# RPi_433MHz_Interface_Board.net
KiCad netlist of a schematic drawn in EAGLE
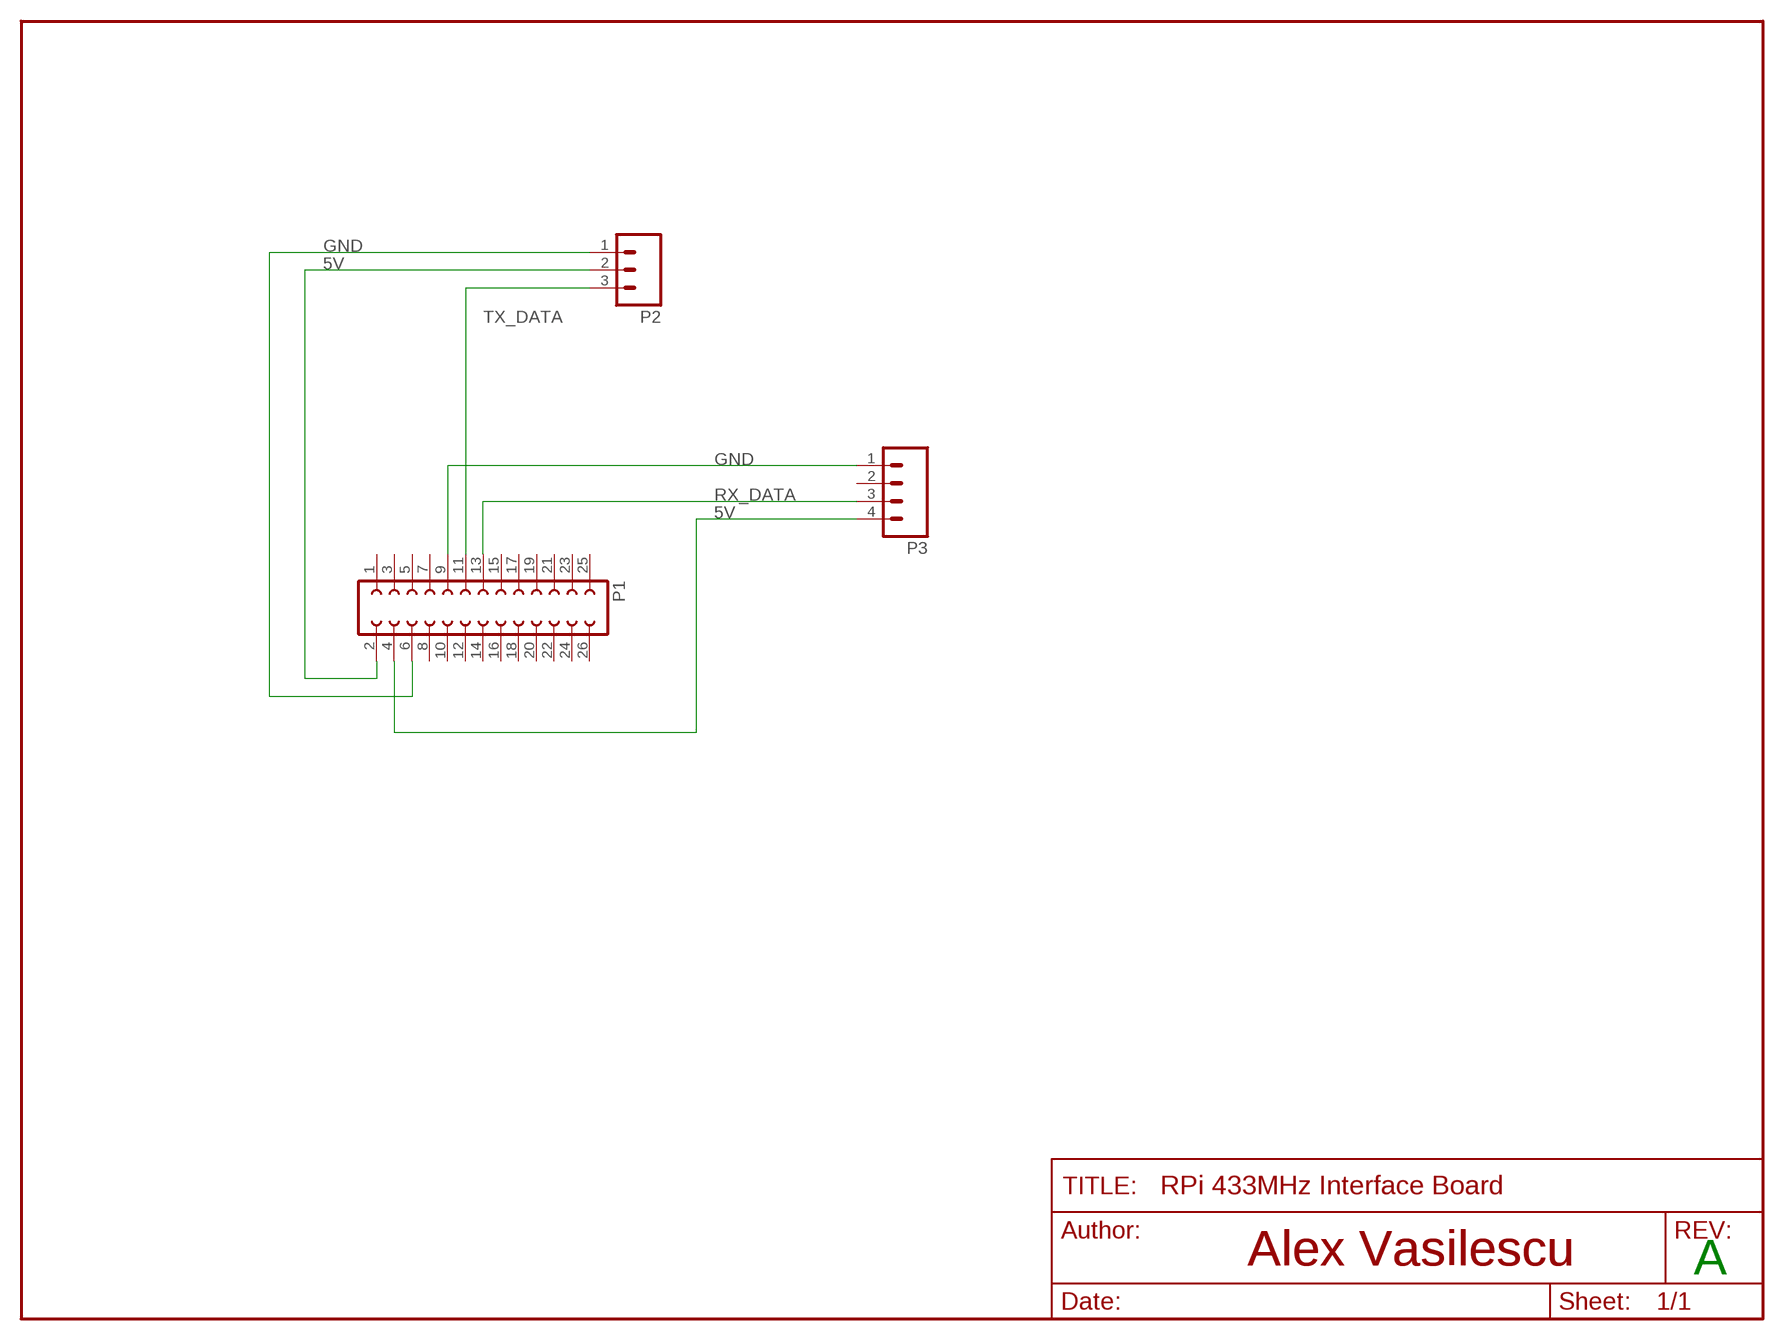
[diagram p0: schematic, sheet 1]

(export (version "E")
  (design (tool "Eeschema 10.0.6"))
  (components
    (comp (ref "P1")
      (value "FE13-2")
      (footprint "eagle-import:FE13-2")
      (libsource (lib "eagle-import") (part "FE13-2"))
    )
    (comp (ref "P2")
      (value "M03POLAR")
      (footprint "eagle-import:MOLEX-1X3")
      (libsource (lib "eagle-import") (part "M03POLAR"))
    )
    (comp (ref "P3")
      (value "M04POLAR")
      (footprint "eagle-import:MOLEX-1X4")
      (libsource (lib "eagle-import") (part "M04POLAR"))
    )
    (comp (ref "U$1")
      (value "AV-LOGO")
      (footprint "eagle-import:AV-LOGO")
      (libsource (lib "eagle-import") (part "AV-LOGO"))
    )
  )
  (nets
    (net (code "1") (name "/5V") (class "Default")
      (node (ref "P1") (pin "2") (pinfunction "2_2") (pintype "passive"))
      (node (ref "P1") (pin "4") (pinfunction "4_4") (pintype "passive"))
      (node (ref "P2") (pin "2") (pinfunction "2_2") (pintype "passive"))
      (node (ref "P3") (pin "4") (pinfunction "4_4") (pintype "passive"))
    )
    (net (code "2") (name "/GND") (class "Default")
      (node (ref "P1") (pin "6") (pinfunction "6_6") (pintype "passive"))
      (node (ref "P1") (pin "9") (pinfunction "9_9") (pintype "passive"))
      (node (ref "P2") (pin "1") (pinfunction "1_1") (pintype "passive"))
      (node (ref "P3") (pin "1") (pinfunction "1_1") (pintype "passive"))
    )
    (net (code "3") (name "/RX_DATA") (class "Default")
      (node (ref "P1") (pin "13") (pinfunction "13_13") (pintype "passive"))
      (node (ref "P3") (pin "3") (pinfunction "3_3") (pintype "passive"))
    )
    (net (code "4") (name "/TX_DATA") (class "Default")
      (node (ref "P1") (pin "11") (pinfunction "11_11") (pintype "passive"))
      (node (ref "P2") (pin "3") (pinfunction "3_3") (pintype "passive"))
    )
    (net (code "5") (name "unconnected-(P1-Pad1)") (class "Default")
      (node (ref "P1") (pin "1") (pinfunction "1_1") (pintype "passive"))
    )
    (net (code "6") (name "unconnected-(P1-Pad3)") (class "Default")
      (node (ref "P1") (pin "3") (pinfunction "3_3") (pintype "passive"))
    )
    (net (code "7") (name "unconnected-(P1-Pad5)") (class "Default")
      (node (ref "P1") (pin "5") (pinfunction "5_5") (pintype "passive"))
    )
    (net (code "8") (name "unconnected-(P1-Pad7)") (class "Default")
      (node (ref "P1") (pin "7") (pinfunction "7_7") (pintype "passive"))
    )
    (net (code "9") (name "unconnected-(P1-Pad8)") (class "Default")
      (node (ref "P1") (pin "8") (pinfunction "8_8") (pintype "passive"))
    )
    (net (code "10") (name "unconnected-(P1-Pad10)") (class "Default")
      (node (ref "P1") (pin "10") (pinfunction "10_10") (pintype "passive"))
    )
    (net (code "11") (name "unconnected-(P1-Pad12)") (class "Default")
      (node (ref "P1") (pin "12") (pinfunction "12_12") (pintype "passive"))
    )
    (net (code "12") (name "unconnected-(P1-Pad14)") (class "Default")
      (node (ref "P1") (pin "14") (pinfunction "14_14") (pintype "passive"))
    )
    (net (code "13") (name "unconnected-(P1-Pad15)") (class "Default")
      (node (ref "P1") (pin "15") (pinfunction "15_15") (pintype "passive"))
    )
    (net (code "14") (name "unconnected-(P1-Pad16)") (class "Default")
      (node (ref "P1") (pin "16") (pinfunction "16_16") (pintype "passive"))
    )
    (net (code "15") (name "unconnected-(P1-Pad17)") (class "Default")
      (node (ref "P1") (pin "17") (pinfunction "17_17") (pintype "passive"))
    )
    (net (code "16") (name "unconnected-(P1-Pad18)") (class "Default")
      (node (ref "P1") (pin "18") (pinfunction "18_18") (pintype "passive"))
    )
    (net (code "17") (name "unconnected-(P1-Pad19)") (class "Default")
      (node (ref "P1") (pin "19") (pinfunction "19_19") (pintype "passive"))
    )
    (net (code "18") (name "unconnected-(P1-Pad20)") (class "Default")
      (node (ref "P1") (pin "20") (pinfunction "20_20") (pintype "passive"))
    )
    (net (code "19") (name "unconnected-(P1-Pad21)") (class "Default")
      (node (ref "P1") (pin "21") (pinfunction "21_21") (pintype "passive"))
    )
    (net (code "20") (name "unconnected-(P1-Pad22)") (class "Default")
      (node (ref "P1") (pin "22") (pinfunction "22_22") (pintype "passive"))
    )
    (net (code "21") (name "unconnected-(P1-Pad23)") (class "Default")
      (node (ref "P1") (pin "23") (pinfunction "23_23") (pintype "passive"))
    )
    (net (code "22") (name "unconnected-(P1-Pad24)") (class "Default")
      (node (ref "P1") (pin "24") (pinfunction "24_24") (pintype "passive"))
    )
    (net (code "23") (name "unconnected-(P1-Pad25)") (class "Default")
      (node (ref "P1") (pin "25") (pinfunction "25_25") (pintype "passive"))
    )
    (net (code "24") (name "unconnected-(P1-Pad26)") (class "Default")
      (node (ref "P1") (pin "26") (pinfunction "26_26") (pintype "passive"))
    )
    (net (code "25") (name "unconnected-(P3-Pad2)") (class "Default")
      (node (ref "P3") (pin "2") (pinfunction "2_2") (pintype "passive"))
    )
  )
)
